# Kill_Board_Top.net
KiCad netlist of a schematic drawn in Altium Designer
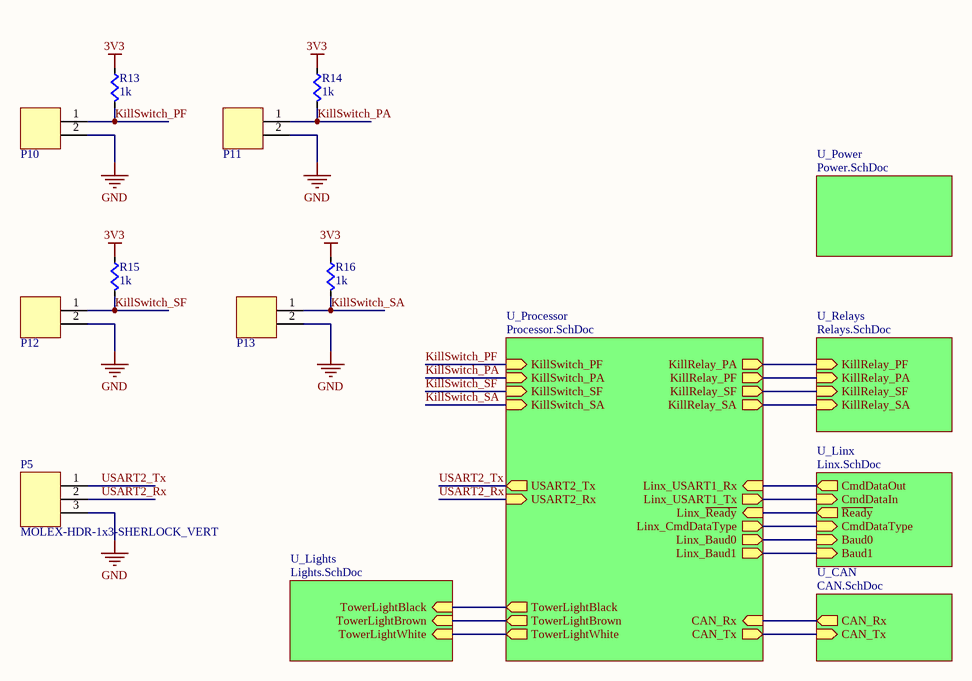
[diagram p0: Kill_Board_Top.SchDoc]

(export (version "E")
  (design (tool "Eeschema 10.0.6"))
  (components
    (comp (ref "P5")
      (value "MOLEX-HDR-1x3-SHERLOCK_VERT")
      (footprint "MOLEX-HDR-1X3-SHERLOCK-VERT")
      (libsource (lib "Connectors") (part "MOLEX-HDR-1x3-SHERLOCK_VERT"))
    )
    (comp (ref "P10")
      (value "2-pin Horz Sherlock")
      (footprint "MOLEX-HDR-1X2-SHERLOCK-HORZ")
      (fields
        (field (name "MANUFACTURER PART NUMBER") "0353630260")
        (field (name "MANUFACTURER") "Molex Inc")
      )
      (libsource (lib "Connectors") (part "MOLEX-HDR-1x2-SHERLOCK_RA"))
    )
    (comp (ref "P11")
      (value "2-pin Horz Sherlock")
      (footprint "MOLEX-HDR-1X2-SHERLOCK-HORZ")
      (fields
        (field (name "MANUFACTURER PART NUMBER") "0353630260")
        (field (name "MANUFACTURER") "Molex Inc")
      )
      (libsource (lib "Connectors") (part "MOLEX-HDR-1x2-SHERLOCK_RA"))
    )
    (comp (ref "P12")
      (value "2-pin Horz Sherlock")
      (footprint "MOLEX-HDR-1X2-SHERLOCK-HORZ")
      (fields
        (field (name "MANUFACTURER PART NUMBER") "0353630260")
        (field (name "MANUFACTURER") "Molex Inc")
      )
      (libsource (lib "Connectors") (part "MOLEX-HDR-1x2-SHERLOCK_RA"))
    )
    (comp (ref "P13")
      (value "2-pin Horz Sherlock")
      (footprint "MOLEX-HDR-1X2-SHERLOCK-HORZ")
      (fields
        (field (name "MANUFACTURER PART NUMBER") "0353630260")
        (field (name "MANUFACTURER") "Molex Inc")
      )
      (libsource (lib "Connectors") (part "MOLEX-HDR-1x2-SHERLOCK_RA"))
    )
    (comp (ref "R13")
      (value "1k")
      (footprint "RES0603")
      (fields (field (name "Comment") "Res"))
      (libsource (lib "SubjuGator8") (part "Res"))
    )
    (comp (ref "R14")
      (value "1k")
      (footprint "RES0603")
      (fields (field (name "Comment") "Res"))
      (libsource (lib "SubjuGator8") (part "Res"))
    )
    (comp (ref "R15")
      (value "1k")
      (footprint "RES0603")
      (fields (field (name "Comment") "Res"))
      (libsource (lib "SubjuGator8") (part "Res"))
    )
    (comp (ref "R16")
      (value "1k")
      (footprint "RES0603")
      (fields (field (name "Comment") "Res"))
      (libsource (lib "SubjuGator8") (part "Res"))
    )
  )
  (nets
    (net (code "8") (name "/KillSwitch_PA") (class "Default")
      (node (ref "P11") (pin "1") (pinfunction "1_1") (pintype "passive"))
      (node (ref "R14") (pin "1") (pinfunction "A_1") (pintype "passive"))
    )
    (net (code "9") (name "/KillSwitch_PF") (class "Default")
      (node (ref "P10") (pin "1") (pinfunction "1_1") (pintype "passive"))
      (node (ref "R13") (pin "1") (pinfunction "A_1") (pintype "passive"))
    )
    (net (code "10") (name "/KillSwitch_SA") (class "Default")
      (node (ref "P13") (pin "1") (pinfunction "1_1") (pintype "passive"))
      (node (ref "R16") (pin "1") (pinfunction "A_1") (pintype "passive"))
    )
    (net (code "11") (name "/KillSwitch_SF") (class "Default")
      (node (ref "P12") (pin "1") (pinfunction "1_1") (pintype "passive"))
      (node (ref "R15") (pin "1") (pinfunction "A_1") (pintype "passive"))
    )
    (net (code "19") (name "/USART2_Rx") (class "Default")
      (node (ref "P5") (pin "2") (pinfunction "2_2") (pintype "passive"))
    )
    (net (code "20") (name "/USART2_Tx") (class "Default")
      (node (ref "P5") (pin "1") (pinfunction "1_1") (pintype "passive"))
    )
    (net (code "22") (name "3V3") (class "Default")
      (node (ref "R13") (pin "2") (pinfunction "B_2") (pintype "passive"))
      (node (ref "R14") (pin "2") (pinfunction "B_2") (pintype "passive"))
      (node (ref "R15") (pin "2") (pinfunction "B_2") (pintype "passive"))
      (node (ref "R16") (pin "2") (pinfunction "B_2") (pintype "passive"))
    )
    (net (code "23") (name "GND") (class "Default")
      (node (ref "P10") (pin "2") (pinfunction "2_2") (pintype "passive"))
      (node (ref "P11") (pin "2") (pinfunction "2_2") (pintype "passive"))
      (node (ref "P12") (pin "2") (pinfunction "2_2") (pintype "passive"))
      (node (ref "P13") (pin "2") (pinfunction "2_2") (pintype "passive"))
      (node (ref "P5") (pin "3") (pinfunction "3_3") (pintype "passive"))
    )
  )
)
